# openSX70-dongle_v5-dual-led.net
KiCad netlist of a schematic drawn in EAGLE
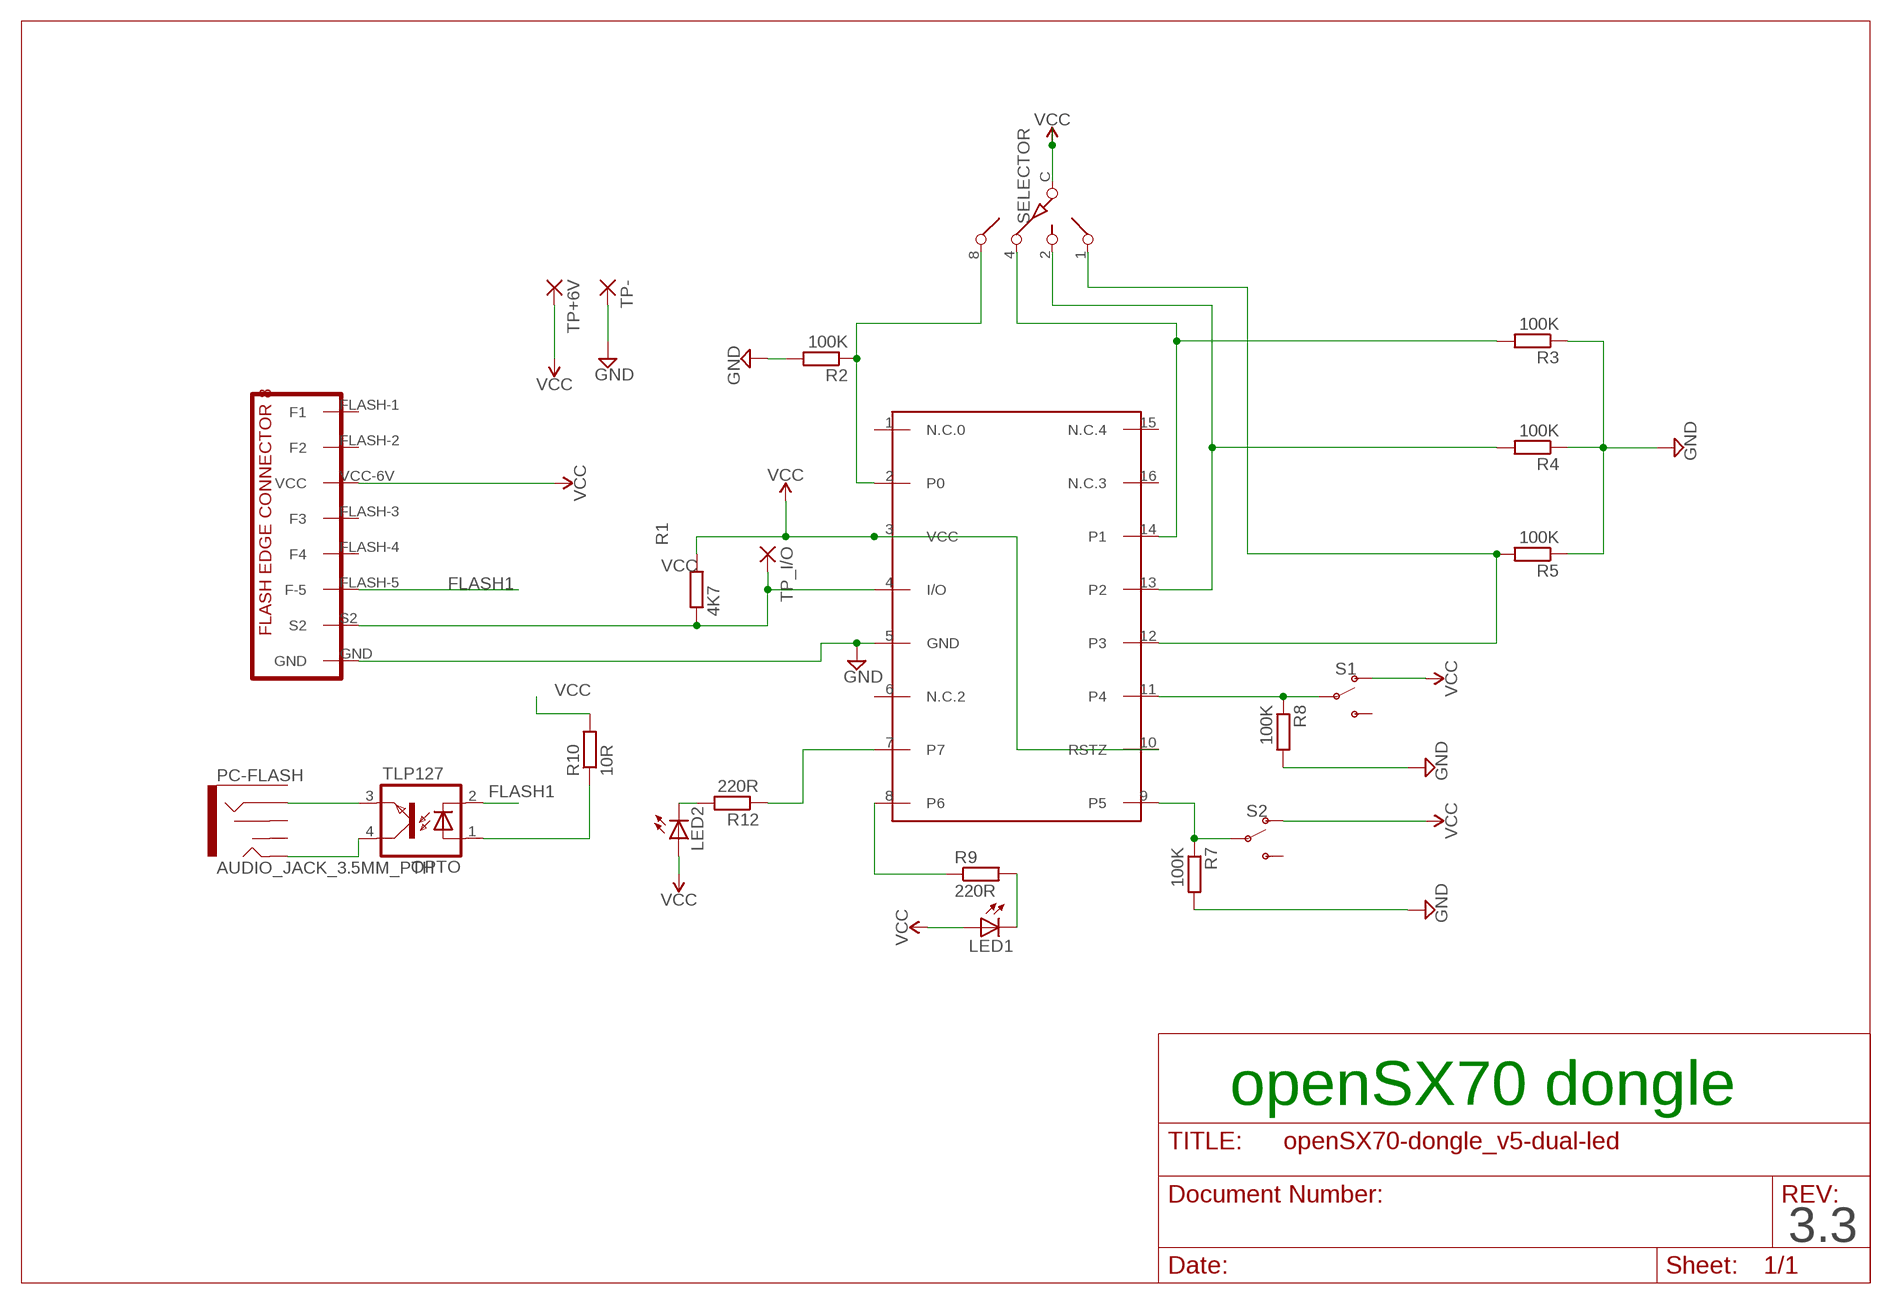
[diagram p0: schematic, sheet 1]

(export (version "E")
  (design (tool "Eeschema 10.0.6"))
  (components
    (comp (ref "DS2408")
      (value "DS2408")
      (footprint "eagle-import:SO16")
      (libsource (lib "eagle-import") (part "DS2408"))
    )
    (comp (ref "LED1")
      (value "LED3MM")
      (footprint "eagle-import:LED3MM")
      (libsource (lib "eagle-import") (part "LED3MM"))
    )
    (comp (ref "LED2")
      (value "LED3MM")
      (footprint "eagle-import:LED3MM")
      (libsource (lib "eagle-import") (part "LED3MM"))
    )
    (comp (ref "OPTO")
      (value "TLP127")
      (footprint "eagle-import:SO-4")
      (libsource (lib "eagle-import") (part "TLP127"))
    )
    (comp (ref "PC-FLASH")
      (value "AUDIO_JACK_3.5MM_PTH")
      (footprint "eagle-import:AUDIO-JACK")
      (libsource (lib "eagle-import") (part "AUDIO_JACK_3.5MM_PTH"))
    )
    (comp (ref "R1")
      (value "4K7")
      (footprint "eagle-import:R0603")
      (libsource (lib "eagle-import") (part "R-EU_R0603"))
    )
    (comp (ref "R2")
      (value "100K")
      (footprint "eagle-import:R0603")
      (libsource (lib "eagle-import") (part "R-EU_R0603"))
    )
    (comp (ref "R3")
      (value "100K")
      (footprint "eagle-import:R0603")
      (libsource (lib "eagle-import") (part "R-EU_R0603"))
    )
    (comp (ref "R4")
      (value "100K")
      (footprint "eagle-import:R0603")
      (libsource (lib "eagle-import") (part "R-EU_R0603"))
    )
    (comp (ref "R5")
      (value "100K")
      (footprint "eagle-import:R0603")
      (libsource (lib "eagle-import") (part "R-EU_R0603"))
    )
    (comp (ref "R7")
      (value "100K")
      (footprint "eagle-import:R0603")
      (libsource (lib "eagle-import") (part "R-EU_R0603"))
    )
    (comp (ref "R8")
      (value "100K")
      (footprint "eagle-import:R0603")
      (libsource (lib "eagle-import") (part "R-EU_R0603"))
    )
    (comp (ref "R9")
      (value "220R")
      (footprint "eagle-import:R0603")
      (libsource (lib "eagle-import") (part "R-EU_R0603"))
    )
    (comp (ref "R10")
      (value "10R")
      (footprint "eagle-import:R0603")
      (libsource (lib "eagle-import") (part "resistor_348_R-EU_R0603"))
    )
    (comp (ref "R12")
      (value "220R")
      (footprint "eagle-import:R0603")
      (libsource (lib "eagle-import") (part "R-EU_R0603"))
    )
    (comp (ref "S1")
      (value "SWITCH-SPDT-SMD-RIGHT-ANGLE")
      (footprint "eagle-import:SWITCH_SPST_SMD_A")
      (libsource (lib "eagle-import") (part "SWITCH-SPDT-SMD-RIGHT-ANGLE"))
    )
    (comp (ref "S2")
      (value "SWITCH-SPDT-SMD-RIGHT-ANGLE")
      (footprint "eagle-import:SWITCH_SPST_SMD_A")
      (libsource (lib "eagle-import") (part "SWITCH-SPDT-SMD-RIGHT-ANGLE"))
    )
    (comp (ref "SELECTOR")
      (value "SW-C16")
      (footprint "eagle-import:SW-C16")
      (libsource (lib "eagle-import") (part "SW-C16"))
    )
    (comp (ref "TP+6V")
      (value "SMD2")
      (footprint "eagle-import:SMD1,27-2,54")
      (libsource (lib "eagle-import") (part "SMD2"))
    )
    (comp (ref "TP-")
      (value "SMD2")
      (footprint "eagle-import:SMD1,27-2,54")
      (libsource (lib "eagle-import") (part "SMD2"))
    )
    (comp (ref "TP_I/O")
      (value "SMD2")
      (footprint "eagle-import:SMD1,27-2,54")
      (libsource (lib "eagle-import") (part "SMD2"))
    )
    (comp (ref "U$2")
      (value "SX70-FLASH-EDGE8-MALE-PROPER")
      (footprint "eagle-import:SX70-FLASH-EDGE8")
      (libsource (lib "eagle-import") (part "SX70-FLASH-EDGE8-MALE-PROPER"))
    )
  )
  (nets
    (net (code "1") (name "/FLASH1") (class "Default")
      (node (ref "OPTO") (pin "1") (pinfunction "A_1") (pintype "passive"))
      (node (ref "OPTO") (pin "2") (pinfunction "C_2") (pintype "passive"))
      (node (ref "R10") (pin "1") (pinfunction "1_1") (pintype "passive"))
      (node (ref "U$2") (pin "FLASH-5") (pinfunction "F-5_FLASH-5") (pintype "bidirectional"))
    )
    (net (code "2") (name "GND") (class "Default")
      (node (ref "DS2408") (pin "5") (pinfunction "GND_5") (pintype "bidirectional"))
      (node (ref "R2") (pin "2") (pinfunction "2_2") (pintype "passive"))
      (node (ref "R3") (pin "1") (pinfunction "1_1") (pintype "passive"))
      (node (ref "R4") (pin "1") (pinfunction "1_1") (pintype "passive"))
      (node (ref "R5") (pin "1") (pinfunction "1_1") (pintype "passive"))
      (node (ref "R7") (pin "2") (pinfunction "2_2") (pintype "passive"))
      (node (ref "R8") (pin "2") (pinfunction "2_2") (pintype "passive"))
      (node (ref "TP-") (pin "1") (pinfunction "P_1") (pintype "passive"))
      (node (ref "U$2") (pin "GND") (pinfunction "GND_GND") (pintype "bidirectional"))
    )
    (net (code "3") (name "Net-(DS2408-I{slash}O)") (class "Default")
      (node (ref "DS2408") (pin "4") (pinfunction "I/O_4") (pintype "bidirectional"))
      (node (ref "R1") (pin "1") (pinfunction "1_1") (pintype "passive"))
      (node (ref "TP_I/O") (pin "1") (pinfunction "P_1") (pintype "passive"))
      (node (ref "U$2") (pin "S2") (pinfunction "S2_S2") (pintype "bidirectional"))
    )
    (net (code "4") (name "Net-(DS2408-P0)") (class "Default")
      (node (ref "DS2408") (pin "2") (pinfunction "P0_2") (pintype "bidirectional"))
      (node (ref "R2") (pin "1") (pinfunction "1_1") (pintype "passive"))
      (node (ref "SELECTOR") (pin "8") (pinfunction "8_8") (pintype "passive"))
    )
    (net (code "5") (name "Net-(DS2408-P1)") (class "Default")
      (node (ref "DS2408") (pin "14") (pinfunction "P1_14") (pintype "bidirectional"))
      (node (ref "R3") (pin "2") (pinfunction "2_2") (pintype "passive"))
      (node (ref "SELECTOR") (pin "4") (pinfunction "4_4") (pintype "passive"))
    )
    (net (code "6") (name "Net-(DS2408-P2)") (class "Default")
      (node (ref "DS2408") (pin "13") (pinfunction "P2_13") (pintype "bidirectional"))
      (node (ref "R4") (pin "2") (pinfunction "2_2") (pintype "passive"))
      (node (ref "SELECTOR") (pin "2") (pinfunction "2_2") (pintype "passive"))
    )
    (net (code "7") (name "Net-(DS2408-P3)") (class "Default")
      (node (ref "DS2408") (pin "12") (pinfunction "P3_12") (pintype "bidirectional"))
      (node (ref "R5") (pin "2") (pinfunction "2_2") (pintype "passive"))
      (node (ref "SELECTOR") (pin "1") (pinfunction "1_1") (pintype "passive"))
    )
    (net (code "8") (name "Net-(DS2408-P4)") (class "Default")
      (node (ref "DS2408") (pin "11") (pinfunction "P4_11") (pintype "bidirectional"))
      (node (ref "R8") (pin "1") (pinfunction "1_1") (pintype "passive"))
      (node (ref "S1") (pin "2") (pinfunction "P_2") (pintype "passive"))
    )
    (net (code "9") (name "Net-(DS2408-P5)") (class "Default")
      (node (ref "DS2408") (pin "9") (pinfunction "P5_9") (pintype "bidirectional"))
      (node (ref "R7") (pin "1") (pinfunction "1_1") (pintype "passive"))
      (node (ref "S2") (pin "2") (pinfunction "P_2") (pintype "passive"))
    )
    (net (code "10") (name "Net-(DS2408-P6)") (class "Default")
      (node (ref "DS2408") (pin "8") (pinfunction "P6_8") (pintype "bidirectional"))
      (node (ref "R9") (pin "1") (pinfunction "1_1") (pintype "passive"))
    )
    (net (code "11") (name "Net-(DS2408-P7)") (class "Default")
      (node (ref "DS2408") (pin "7") (pinfunction "P7_7") (pintype "bidirectional"))
      (node (ref "R12") (pin "1") (pinfunction "1_1") (pintype "passive"))
    )
    (net (code "12") (name "Net-(LED1-C)") (class "Default")
      (node (ref "LED1") (pin "K") (pinfunction "C_K") (pintype "passive"))
      (node (ref "R9") (pin "2") (pinfunction "2_2") (pintype "passive"))
    )
    (net (code "13") (name "Net-(LED2-C)") (class "Default")
      (node (ref "LED2") (pin "K") (pinfunction "C_K") (pintype "passive"))
      (node (ref "R12") (pin "2") (pinfunction "2_2") (pintype "passive"))
    )
    (net (code "14") (name "Net-(OPTO-COL)") (class "Default")
      (node (ref "OPTO") (pin "4") (pinfunction "COL_4") (pintype "passive"))
      (node (ref "PC-FLASH") (pin "TIP") (pinfunction "TIP_TIP") (pintype "bidirectional"))
    )
    (net (code "15") (name "Net-(OPTO-EMIT)") (class "Default")
      (node (ref "OPTO") (pin "3") (pinfunction "EMIT_3") (pintype "passive"))
      (node (ref "PC-FLASH") (pin "RING") (pinfunction "RING_RING") (pintype "bidirectional"))
    )
    (net (code "16") (name "VCC") (class "Default")
      (node (ref "DS2408") (pin "10") (pinfunction "RSTZ_10") (pintype "bidirectional"))
      (node (ref "DS2408") (pin "3") (pinfunction "VCC_3") (pintype "bidirectional"))
      (node (ref "LED1") (pin "A") (pinfunction "A_A") (pintype "passive"))
      (node (ref "LED2") (pin "A") (pinfunction "A_A") (pintype "passive"))
      (node (ref "R1") (pin "2") (pinfunction "2_2") (pintype "passive"))
      (node (ref "R10") (pin "2") (pinfunction "2_2") (pintype "passive"))
      (node (ref "S1") (pin "1") (pinfunction "O_1") (pintype "passive"))
      (node (ref "S2") (pin "1") (pinfunction "O_1") (pintype "passive"))
      (node (ref "SELECTOR") (pin "C") (pinfunction "C_C") (pintype "passive"))
      (node (ref "TP+6V") (pin "1") (pinfunction "P_1") (pintype "passive"))
      (node (ref "U$2") (pin "VCC-6V") (pinfunction "VCC_VCC-6V") (pintype "bidirectional"))
    )
    (net (code "17") (name "unconnected-(DS2408-N.C.0-Pad1)") (class "Default")
      (node (ref "DS2408") (pin "1") (pinfunction "N.C.0_1") (pintype "bidirectional"))
    )
    (net (code "18") (name "unconnected-(DS2408-N.C.2-Pad6)") (class "Default")
      (node (ref "DS2408") (pin "6") (pinfunction "N.C.2_6") (pintype "bidirectional"))
    )
    (net (code "19") (name "unconnected-(DS2408-N.C.3-Pad16)") (class "Default")
      (node (ref "DS2408") (pin "16") (pinfunction "N.C.3_16") (pintype "bidirectional"))
    )
    (net (code "20") (name "unconnected-(DS2408-N.C.4-Pad15)") (class "Default")
      (node (ref "DS2408") (pin "15") (pinfunction "N.C.4_15") (pintype "bidirectional"))
    )
    (net (code "21") (name "unconnected-(PC-FLASH-PadRSH)") (class "Default")
      (node (ref "PC-FLASH") (pin "RSH") (pinfunction "RSH_RSH") (pintype "bidirectional"))
    )
    (net (code "22") (name "unconnected-(PC-FLASH-PadSLEEVE)") (class "Default")
      (node (ref "PC-FLASH") (pin "SLEEVE") (pinfunction "SLEEVE_SLEEVE") (pintype "bidirectional"))
    )
    (net (code "23") (name "unconnected-(PC-FLASH-PadTSH)") (class "Default")
      (node (ref "PC-FLASH") (pin "TSH") (pinfunction "TSH_TSH") (pintype "bidirectional"))
    )
    (net (code "24") (name "unconnected-(S1-S-Pad3)") (class "Default")
      (node (ref "S1") (pin "3") (pinfunction "S_3") (pintype "passive"))
    )
    (net (code "25") (name "unconnected-(S2-S-Pad3)") (class "Default")
      (node (ref "S2") (pin "3") (pinfunction "S_3") (pintype "passive"))
    )
    (net (code "26") (name "unconnected-(U$2-F1-PadFLASH-1)") (class "Default")
      (node (ref "U$2") (pin "FLASH-1") (pinfunction "F1_FLASH-1") (pintype "bidirectional"))
    )
    (net (code "27") (name "unconnected-(U$2-F2-PadFLASH-2)") (class "Default")
      (node (ref "U$2") (pin "FLASH-2") (pinfunction "F2_FLASH-2") (pintype "bidirectional"))
    )
    (net (code "28") (name "unconnected-(U$2-F3-PadFLASH-3)") (class "Default")
      (node (ref "U$2") (pin "FLASH-3") (pinfunction "F3_FLASH-3") (pintype "bidirectional"))
    )
    (net (code "29") (name "unconnected-(U$2-F4-PadFLASH-4)") (class "Default")
      (node (ref "U$2") (pin "FLASH-4") (pinfunction "F4_FLASH-4") (pintype "bidirectional"))
    )
  )
)
